# HMS_Olfactometer_v2_1.net
KiCad netlist of a schematic drawn in EAGLE
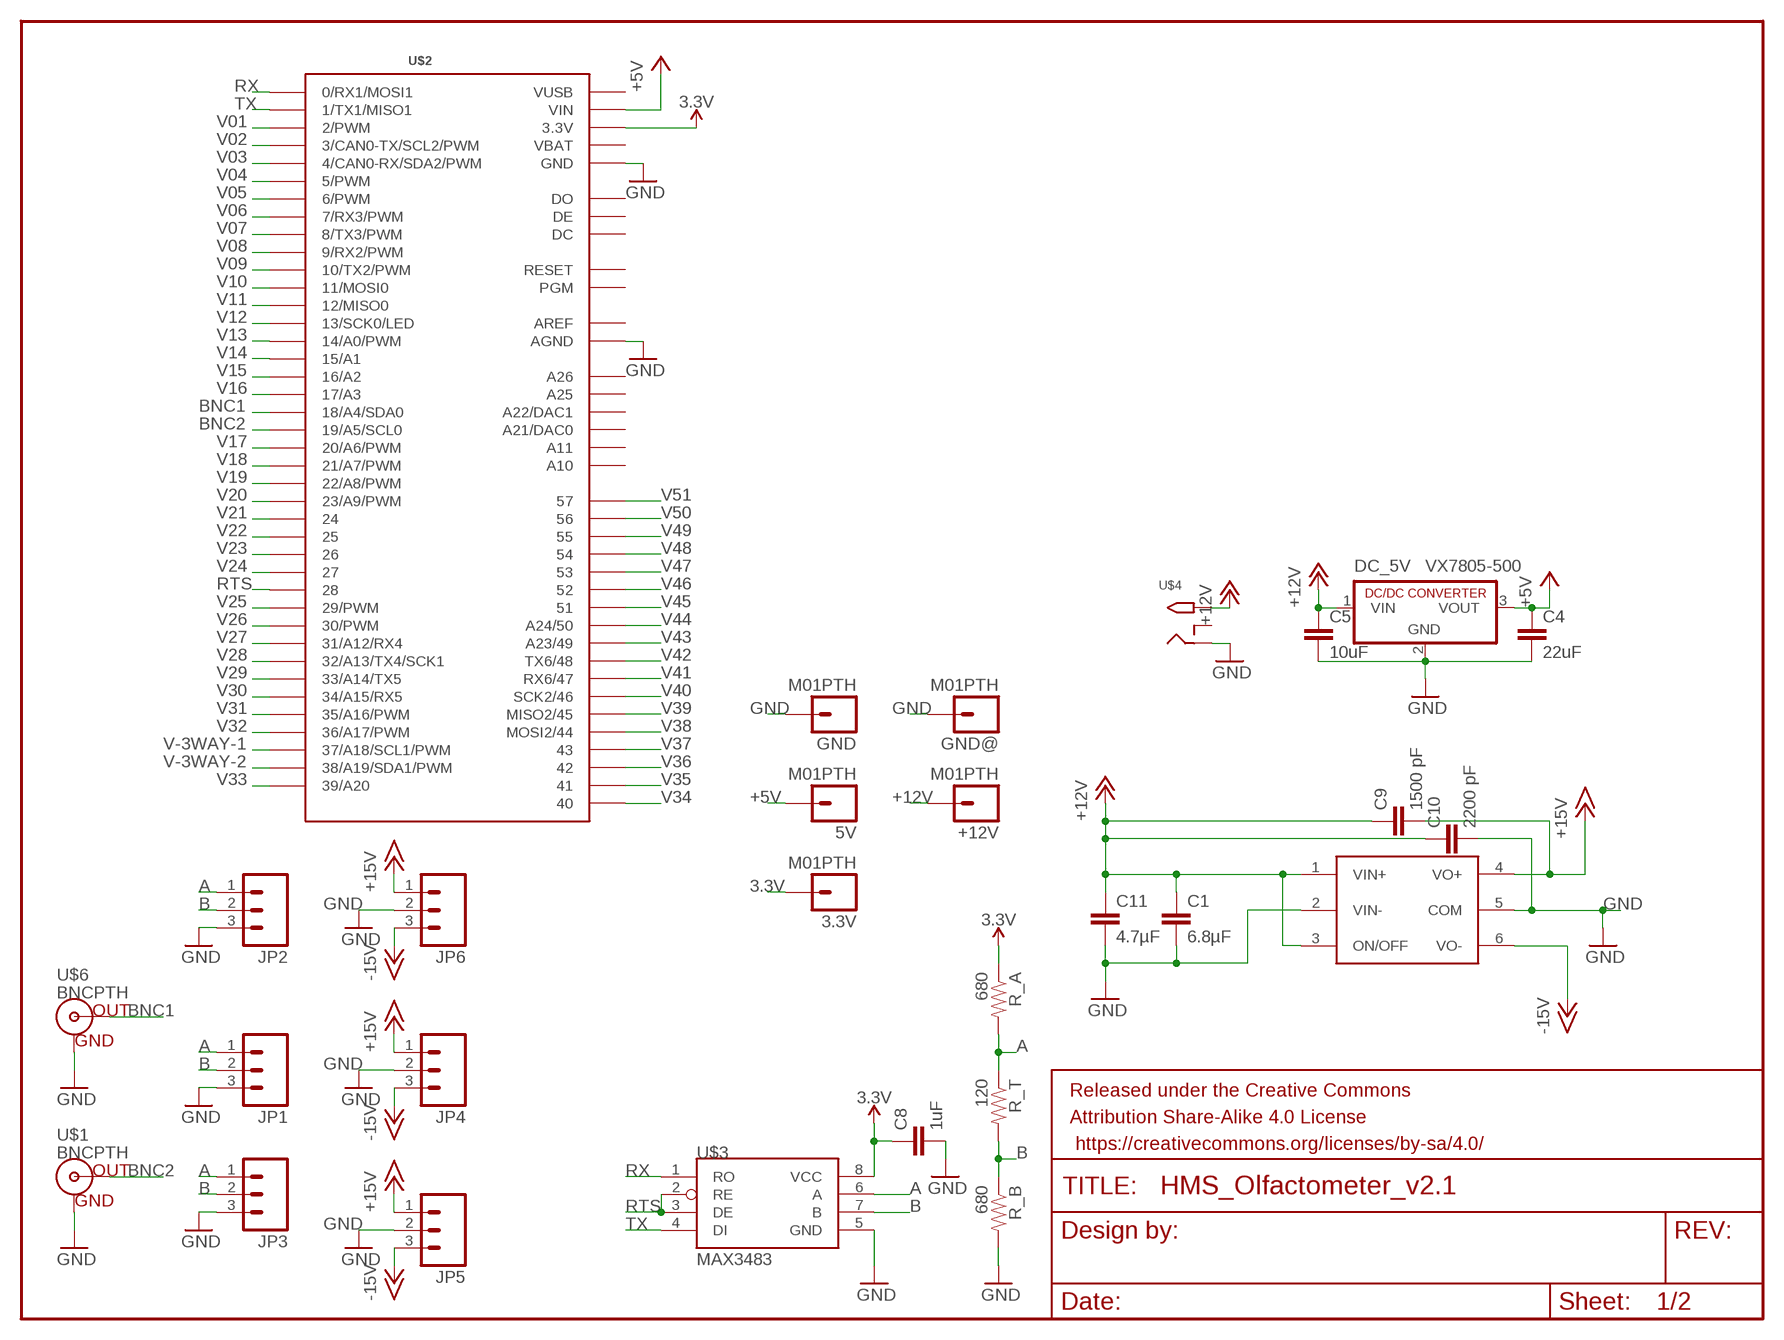
[diagram p0: schematic, sheet 1]
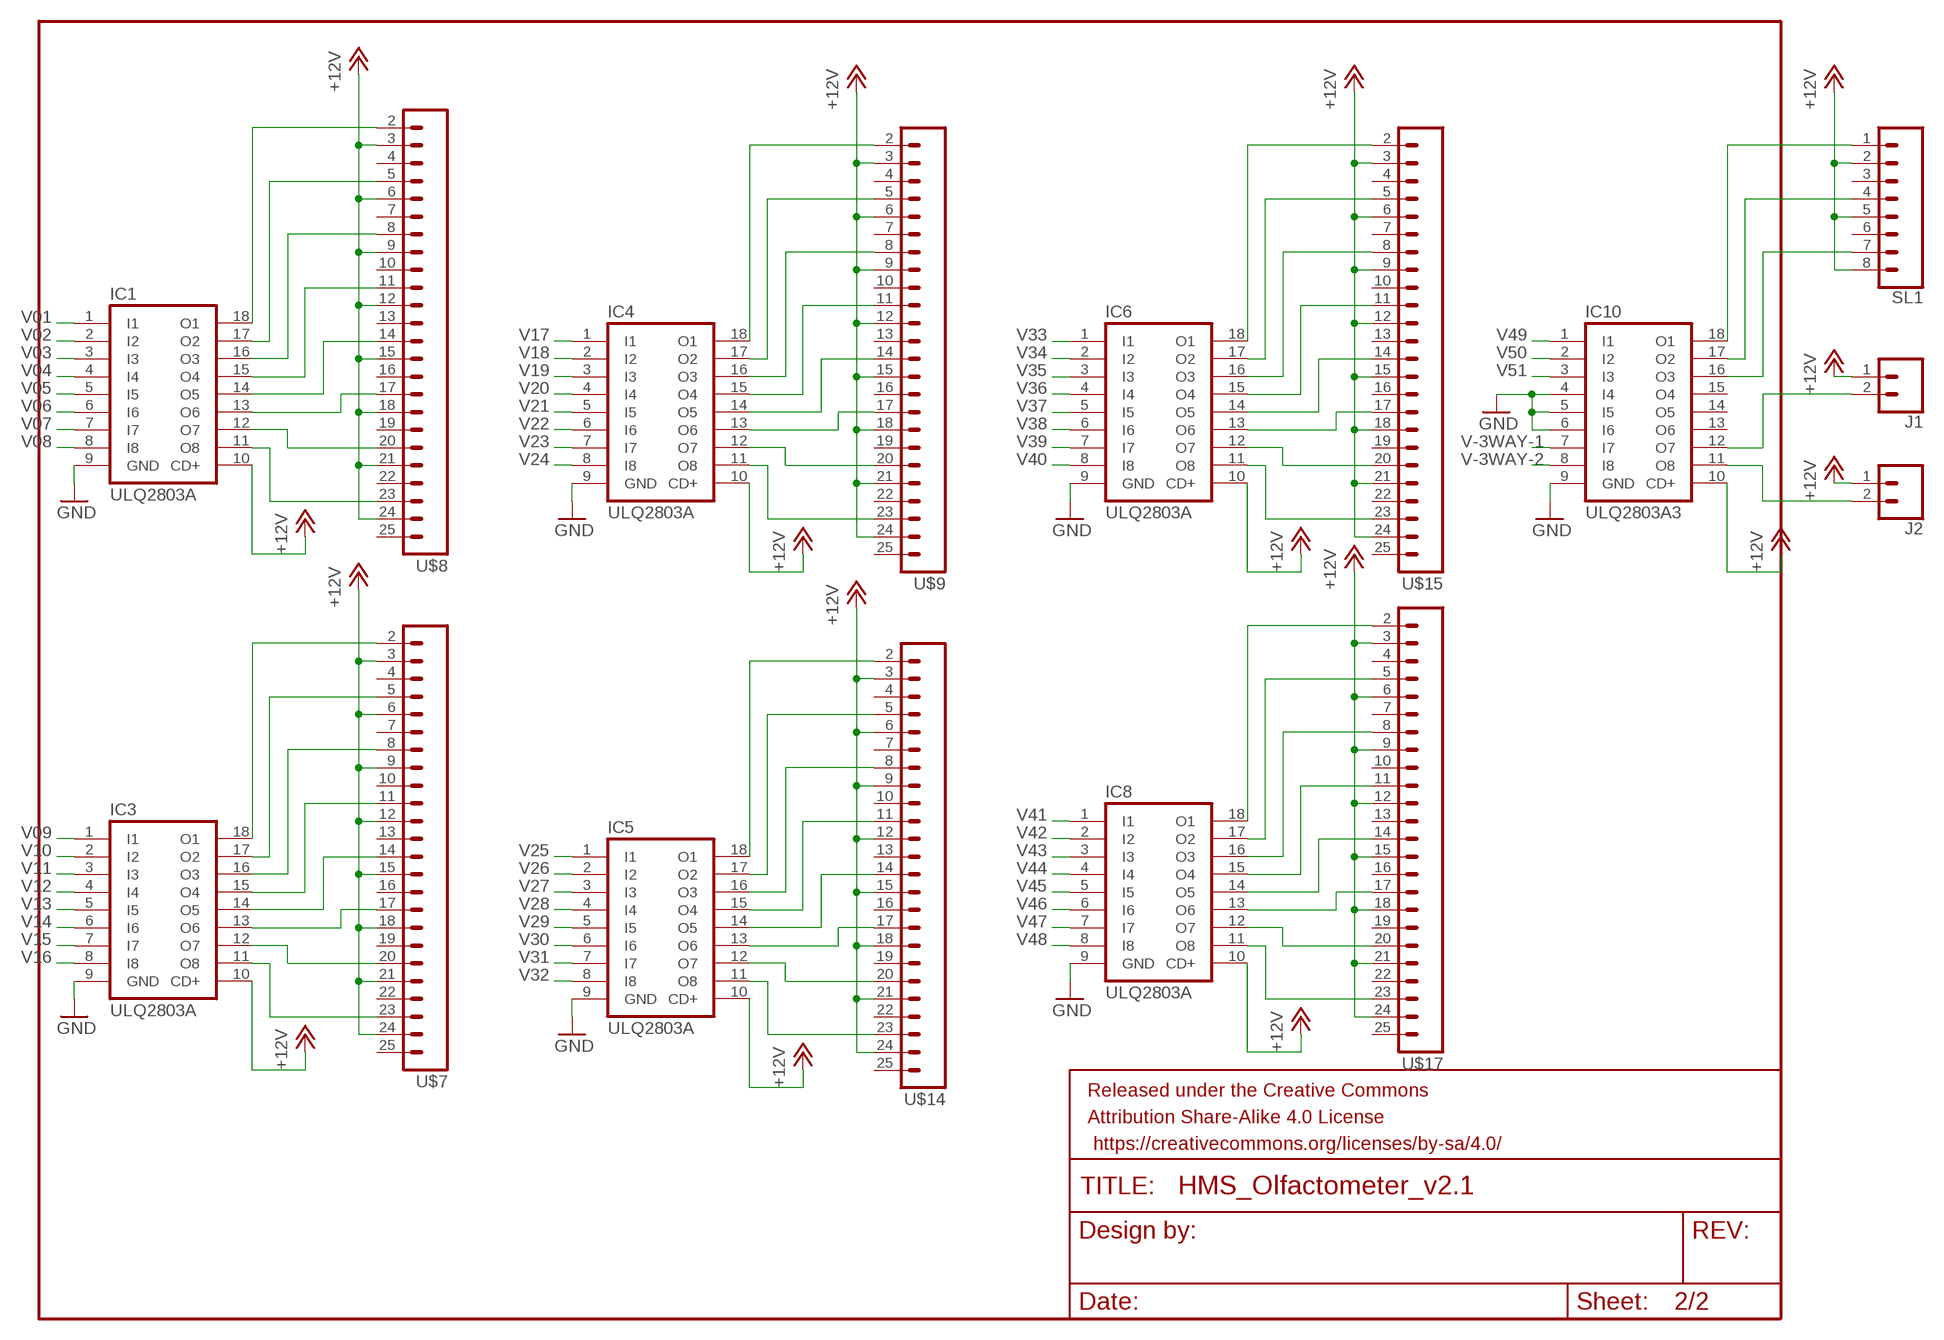
[diagram p1: schematic, sheet 2]

(export (version "E")
  (design (tool "Eeschema 10.0.6"))
  (components
    (comp (ref "FRAME2")
      (value "FRAME-LETTER")
      (footprint "eagle-import:CREATIVE_COMMONS")
      (libsource (lib "eagle-import") (part "FRAME-LETTER"))
    )
    (comp (ref "IC1")
      (value "ULQ2803A")
      (footprint "eagle-import:DIL18")
      (libsource (lib "eagle-import") (part "ULN2803A"))
    )
    (comp (ref "IC3")
      (value "ULQ2803A")
      (footprint "eagle-import:DIL18")
      (libsource (lib "eagle-import") (part "ULN2803A"))
    )
    (comp (ref "IC4")
      (value "ULQ2803A")
      (footprint "eagle-import:DIL18")
      (libsource (lib "eagle-import") (part "ULN2803A"))
    )
    (comp (ref "IC5")
      (value "ULQ2803A")
      (footprint "eagle-import:DIL18")
      (libsource (lib "eagle-import") (part "ULN2803A"))
    )
    (comp (ref "IC6")
      (value "ULQ2803A")
      (footprint "eagle-import:DIL18")
      (libsource (lib "eagle-import") (part "ULN2803A"))
    )
    (comp (ref "IC8")
      (value "ULQ2803A")
      (footprint "eagle-import:DIL18")
      (libsource (lib "eagle-import") (part "ULN2803A"))
    )
    (comp (ref "IC10")
      (value "ULQ2803A3")
      (footprint "eagle-import:DIL18")
      (libsource (lib "eagle-import") (part "ULN2803A"))
    )
    (comp (ref "J1")
      (value "CONN_02")
      (footprint "eagle-import:1X02")
      (libsource (lib "eagle-import") (part "CONN_02"))
    )
    (comp (ref "J2")
      (value "CONN_02")
      (footprint "eagle-import:1X02")
      (libsource (lib "eagle-import") (part "CONN_02"))
    )
    (comp (ref "SL1")
      (value "CONN_08\"")
      (footprint "eagle-import:1X08")
      (libsource (lib "eagle-import") (part "CONN_08{dblquote}"))
    )
    (comp (ref "U$7")
      (value "M24")
      (footprint "eagle-import:1X24")
      (libsource (lib "eagle-import") (part "M24"))
    )
    (comp (ref "U$8")
      (value "M24")
      (footprint "eagle-import:1X24")
      (libsource (lib "eagle-import") (part "M24"))
    )
    (comp (ref "U$9")
      (value "M24")
      (footprint "eagle-import:1X24")
      (libsource (lib "eagle-import") (part "M24"))
    )
    (comp (ref "U$14")
      (value "M24")
      (footprint "eagle-import:1X24")
      (libsource (lib "eagle-import") (part "M24"))
    )
    (comp (ref "U$15")
      (value "M24")
      (footprint "eagle-import:1X24")
      (libsource (lib "eagle-import") (part "M24"))
    )
    (comp (ref "U$17")
      (value "M24")
      (footprint "eagle-import:1X24")
      (libsource (lib "eagle-import") (part "M24"))
    )
    (comp (ref "+12V")
      (value "M01PTH")
      (footprint "eagle-import:1X01")
      (libsource (lib "eagle-import") (part "M01PTH"))
    )
    (comp (ref "3.3V")
      (value "M01PTH")
      (footprint "eagle-import:1X01")
      (libsource (lib "eagle-import") (part "M01PTH"))
    )
    (comp (ref "5V")
      (value "M01PTH")
      (footprint "eagle-import:1X01")
      (libsource (lib "eagle-import") (part "M01PTH"))
    )
    (comp (ref "C1")
      (value "6.8µF")
      (footprint "eagle-import:C1812")
      (libsource (lib "eagle-import") (part "C-EUC1812"))
    )
    (comp (ref "C4")
      (value "22uF")
      (footprint "eagle-import:1206")
      (libsource (lib "eagle-import") (part "10UF-6.3V-20%(1206)"))
    )
    (comp (ref "C5")
      (value "10uF")
      (footprint "eagle-import:1206")
      (libsource (lib "eagle-import") (part "CAP1206"))
    )
    (comp (ref "C8")
      (value "1uF")
      (footprint "eagle-import:1206")
      (libsource (lib "eagle-import") (part "CAP1206"))
    )
    (comp (ref "C9")
      (value "1500 pF")
      (footprint "eagle-import:C1206")
      (libsource (lib "eagle-import") (part "C-EUC1206"))
    )
    (comp (ref "C10")
      (value "2200 pF")
      (footprint "eagle-import:C1206")
      (libsource (lib "eagle-import") (part "C-EUC1206"))
    )
    (comp (ref "C11")
      (value "4.7µF")
      (footprint "eagle-import:C1812")
      (libsource (lib "eagle-import") (part "C-EUC1812"))
    )
    (comp (ref "DC_+/-15V")
      (value "XPPOWER_+/-15V_60W_DC-DC_SUPPLY")
      (footprint "eagle-import:XPPOWER_60W_JTL60_DC_DC_POWER_SUPPLY")
      (libsource (lib "eagle-import") (part "XPPOWER_+/-15V_60W_DC-DC_SUPPLY"))
    )
    (comp (ref "DC_5V")
      (value "VX7805-500")
      (footprint "eagle-import:SIP3")
      (libsource (lib "eagle-import") (part "R-78C-1.012"))
    )
    (comp (ref "FRAME1")
      (value "FRAME-LETTER")
      (footprint "eagle-import:CREATIVE_COMMONS")
      (libsource (lib "eagle-import") (part "FRAME-LETTER"))
    )
    (comp (ref "GND")
      (value "M01PTH")
      (footprint "eagle-import:1X01")
      (libsource (lib "eagle-import") (part "M01PTH"))
    )
    (comp (ref "GND@")
      (value "M01PTH")
      (footprint "eagle-import:1X01")
      (libsource (lib "eagle-import") (part "M01PTH"))
    )
    (comp (ref "JP1")
      (value "M03POLAR")
      (footprint "eagle-import:MOLEX-1X3")
      (libsource (lib "eagle-import") (part "M03POLAR"))
    )
    (comp (ref "JP2")
      (value "M03POLAR")
      (footprint "eagle-import:MOLEX-1X3")
      (libsource (lib "eagle-import") (part "M03POLAR"))
    )
    (comp (ref "JP3")
      (value "M03POLAR")
      (footprint "eagle-import:MOLEX-1X3")
      (libsource (lib "eagle-import") (part "M03POLAR"))
    )
    (comp (ref "JP4")
      (value "M03SCREW")
      (footprint "eagle-import:SCREWTERMINAL-3.5MM-3")
      (libsource (lib "eagle-import") (part "M03SCREW"))
    )
    (comp (ref "JP5")
      (value "M03SCREW")
      (footprint "eagle-import:SCREWTERMINAL-3.5MM-3")
      (libsource (lib "eagle-import") (part "M03SCREW"))
    )
    (comp (ref "JP6")
      (value "M03SCREW")
      (footprint "eagle-import:SCREWTERMINAL-3.5MM-3")
      (libsource (lib "eagle-import") (part "M03SCREW"))
    )
    (comp (ref "R_A")
      (value "680")
      (footprint "eagle-import:AXIAL-0.5")
      (libsource (lib "eagle-import") (part "RESISTORPTH-1/2W"))
    )
    (comp (ref "R_B")
      (value "680")
      (footprint "eagle-import:AXIAL-0.5")
      (libsource (lib "eagle-import") (part "RESISTORPTH-1/2W"))
    )
    (comp (ref "R_T")
      (value "120")
      (footprint "eagle-import:AXIAL-0.5")
      (libsource (lib "eagle-import") (part "RESISTORPTH-1/2W"))
    )
    (comp (ref "U$1")
      (value "BNCPTH")
      (footprint "eagle-import:BNC")
      (libsource (lib "eagle-import") (part "BNCPTH"))
    )
    (comp (ref "U$2")
      (value "TEENSY_3.5_ALL_PINS&PADS")
      (footprint "eagle-import:TEENSY_3.5_ALL_PINS&PADS")
      (libsource (lib "eagle-import") (part "TEENSY_3.5_ALL_PINS&PADS"))
    )
    (comp (ref "U$3")
      (value "MAX3483")
      (footprint "eagle-import:DIL08")
      (fields (field (name "SPICEPREFIX") "X"))
      (libsource (lib "eagle-import") (part "MAX485DIL"))
    )
    (comp (ref "U$4")
      (value "2.1MMJACKTHM")
      (footprint "eagle-import:PJ-102A")
      (libsource (lib "eagle-import") (part "2.1MMJACKTHM"))
    )
    (comp (ref "U$6")
      (value "BNCPTH")
      (footprint "eagle-import:BNC")
      (libsource (lib "eagle-import") (part "BNCPTH"))
    )
  )
  (nets
    (net (code "1") (name "+5V") (class "Default")
      (node (ref "5V") (pin "1") (pinfunction "1_1") (pintype "passive"))
      (node (ref "C4") (pin "1") (pinfunction "1_1") (pintype "passive"))
      (node (ref "DC_5V") (pin "3") (pinfunction "VOUT_3") (pintype "passive"))
      (node (ref "U$2") (pin "VIN") (pinfunction "VIN_VIN") (pintype "power_in"))
    )
    (net (code "2") (name "+12V") (class "Default")
      (node (ref "+12V") (pin "1") (pinfunction "1_1") (pintype "passive"))
      (node (ref "C1") (pin "1") (pinfunction "1_1") (pintype "passive"))
      (node (ref "C10") (pin "1") (pinfunction "1_1") (pintype "passive"))
      (node (ref "C11") (pin "1") (pinfunction "1_1") (pintype "passive"))
      (node (ref "C5") (pin "1") (pinfunction "1_1") (pintype "passive"))
      (node (ref "C9") (pin "1") (pinfunction "1_1") (pintype "passive"))
      (node (ref "DC_+/-15V") (pin "1") (pinfunction "VIN+_1") (pintype "passive"))
      (node (ref "DC_+/-15V") (pin "3") (pinfunction "ON/OFF_3") (pintype "bidirectional"))
      (node (ref "DC_5V") (pin "1") (pinfunction "VIN_1") (pintype "passive"))
      (node (ref "IC1") (pin "10") (pinfunction "CD+_10") (pintype "passive"))
      (node (ref "IC10") (pin "10") (pinfunction "CD+_10") (pintype "passive"))
      (node (ref "IC3") (pin "10") (pinfunction "CD+_10") (pintype "passive"))
      (node (ref "IC4") (pin "10") (pinfunction "CD+_10") (pintype "passive"))
      (node (ref "IC5") (pin "10") (pinfunction "CD+_10") (pintype "passive"))
      (node (ref "IC6") (pin "10") (pinfunction "CD+_10") (pintype "passive"))
      (node (ref "IC8") (pin "10") (pinfunction "CD+_10") (pintype "passive"))
      (node (ref "J1") (pin "1") (pinfunction "1_1") (pintype "passive"))
      (node (ref "J2") (pin "1") (pinfunction "1_1") (pintype "passive"))
      (node (ref "SL1") (pin "2") (pinfunction "2_2") (pintype "passive"))
      (node (ref "SL1") (pin "5") (pinfunction "5_5") (pintype "passive"))
      (node (ref "SL1") (pin "8") (pinfunction "8_8") (pintype "passive"))
      (node (ref "U$14") (pin "12") (pinfunction "12_12") (pintype "passive"))
      (node (ref "U$14") (pin "15") (pinfunction "15_15") (pintype "passive"))
      (node (ref "U$14") (pin "18") (pinfunction "18_18") (pintype "passive"))
      (node (ref "U$14") (pin "21") (pinfunction "21_21") (pintype "passive"))
      (node (ref "U$14") (pin "24") (pinfunction "24_24") (pintype "passive"))
      (node (ref "U$14") (pin "3") (pinfunction "3_3") (pintype "passive"))
      (node (ref "U$14") (pin "6") (pinfunction "6_6") (pintype "passive"))
      (node (ref "U$14") (pin "9") (pinfunction "9_9") (pintype "passive"))
      (node (ref "U$15") (pin "12") (pinfunction "12_12") (pintype "passive"))
      (node (ref "U$15") (pin "15") (pinfunction "15_15") (pintype "passive"))
      (node (ref "U$15") (pin "18") (pinfunction "18_18") (pintype "passive"))
      (node (ref "U$15") (pin "21") (pinfunction "21_21") (pintype "passive"))
      (node (ref "U$15") (pin "24") (pinfunction "24_24") (pintype "passive"))
      (node (ref "U$15") (pin "3") (pinfunction "3_3") (pintype "passive"))
      (node (ref "U$15") (pin "6") (pinfunction "6_6") (pintype "passive"))
      (node (ref "U$15") (pin "9") (pinfunction "9_9") (pintype "passive"))
      (node (ref "U$17") (pin "12") (pinfunction "12_12") (pintype "passive"))
      (node (ref "U$17") (pin "15") (pinfunction "15_15") (pintype "passive"))
      (node (ref "U$17") (pin "18") (pinfunction "18_18") (pintype "passive"))
      (node (ref "U$17") (pin "21") (pinfunction "21_21") (pintype "passive"))
      (node (ref "U$17") (pin "24") (pinfunction "24_24") (pintype "passive"))
      (node (ref "U$17") (pin "3") (pinfunction "3_3") (pintype "passive"))
      (node (ref "U$17") (pin "6") (pinfunction "6_6") (pintype "passive"))
      (node (ref "U$17") (pin "9") (pinfunction "9_9") (pintype "passive"))
      (node (ref "U$4") (pin "TIP") (pinfunction "TIP_TIP") (pintype "bidirectional"))
      (node (ref "U$7") (pin "12") (pinfunction "12_12") (pintype "passive"))
      (node (ref "U$7") (pin "15") (pinfunction "15_15") (pintype "passive"))
      (node (ref "U$7") (pin "18") (pinfunction "18_18") (pintype "passive"))
      (node (ref "U$7") (pin "21") (pinfunction "21_21") (pintype "passive"))
      (node (ref "U$7") (pin "24") (pinfunction "24_24") (pintype "passive"))
      (node (ref "U$7") (pin "3") (pinfunction "3_3") (pintype "passive"))
      (node (ref "U$7") (pin "6") (pinfunction "6_6") (pintype "passive"))
      (node (ref "U$7") (pin "9") (pinfunction "9_9") (pintype "passive"))
      (node (ref "U$8") (pin "12") (pinfunction "12_12") (pintype "passive"))
      (node (ref "U$8") (pin "15") (pinfunction "15_15") (pintype "passive"))
      (node (ref "U$8") (pin "18") (pinfunction "18_18") (pintype "passive"))
      (node (ref "U$8") (pin "21") (pinfunction "21_21") (pintype "passive"))
      (node (ref "U$8") (pin "24") (pinfunction "24_24") (pintype "passive"))
      (node (ref "U$8") (pin "3") (pinfunction "3_3") (pintype "passive"))
      (node (ref "U$8") (pin "6") (pinfunction "6_6") (pintype "passive"))
      (node (ref "U$8") (pin "9") (pinfunction "9_9") (pintype "passive"))
      (node (ref "U$9") (pin "12") (pinfunction "12_12") (pintype "passive"))
      (node (ref "U$9") (pin "15") (pinfunction "15_15") (pintype "passive"))
      (node (ref "U$9") (pin "18") (pinfunction "18_18") (pintype "passive"))
      (node (ref "U$9") (pin "21") (pinfunction "21_21") (pintype "passive"))
      (node (ref "U$9") (pin "24") (pinfunction "24_24") (pintype "passive"))
      (node (ref "U$9") (pin "3") (pinfunction "3_3") (pintype "passive"))
      (node (ref "U$9") (pin "6") (pinfunction "6_6") (pintype "passive"))
      (node (ref "U$9") (pin "9") (pinfunction "9_9") (pintype "passive"))
    )
    (net (code "3") (name "+15V") (class "Default")
      (node (ref "C9") (pin "2") (pinfunction "2_2") (pintype "passive"))
      (node (ref "DC_+/-15V") (pin "4") (pinfunction "VO+_4") (pintype "power_in"))
      (node (ref "JP4") (pin "1") (pinfunction "1_1") (pintype "passive"))
      (node (ref "JP5") (pin "1") (pinfunction "1_1") (pintype "passive"))
      (node (ref "JP6") (pin "1") (pinfunction "1_1") (pintype "passive"))
    )
    (net (code "4") (name "-15V") (class "Default")
      (node (ref "DC_+/-15V") (pin "6") (pinfunction "VO-_6") (pintype "power_in"))
      (node (ref "JP4") (pin "3") (pinfunction "3_3") (pintype "passive"))
      (node (ref "JP5") (pin "3") (pinfunction "3_3") (pintype "passive"))
      (node (ref "JP6") (pin "3") (pinfunction "3_3") (pintype "passive"))
    )
    (net (code "5") (name "3.3V") (class "Default")
      (node (ref "3.3V") (pin "1") (pinfunction "1_1") (pintype "passive"))
      (node (ref "C8") (pin "1") (pinfunction "1_1") (pintype "passive"))
      (node (ref "R_A") (pin "P$1") (pinfunction "1_P$1") (pintype "passive"))
      (node (ref "U$2") (pin "3.3V") (pinfunction "3.3V_3.3V") (pintype "power_in"))
      (node (ref "U$2") (pin "3.3V2") (pinfunction "3.3V_3.3V2") (pintype "power_in"))
      (node (ref "U$2") (pin "3.3V3") (pinfunction "3.3V_3.3V3") (pintype "power_in"))
      (node (ref "U$2") (pin "3.3V4") (pinfunction "3.3V_3.3V4") (pintype "power_in"))
      (node (ref "U$3") (pin "8") (pinfunction "VCC_8") (pintype "bidirectional"))
    )
    (net (code "6") (name "A") (class "Default")
      (node (ref "JP1") (pin "1") (pinfunction "1_1") (pintype "passive"))
      (node (ref "JP2") (pin "1") (pinfunction "1_1") (pintype "passive"))
      (node (ref "JP3") (pin "1") (pinfunction "1_1") (pintype "passive"))
      (node (ref "R_A") (pin "P$2") (pinfunction "2_P$2") (pintype "passive"))
      (node (ref "R_T") (pin "P$1") (pinfunction "1_P$1") (pintype "passive"))
      (node (ref "U$3") (pin "6") (pinfunction "A_6") (pintype "bidirectional"))
    )
    (net (code "7") (name "AREF") (class "Default")
      (node (ref "U$2") (pin "AREF") (pinfunction "AREF_AREF") (pintype "power_in"))
    )
    (net (code "8") (name "B") (class "Default")
      (node (ref "JP1") (pin "2") (pinfunction "2_2") (pintype "passive"))
      (node (ref "JP2") (pin "2") (pinfunction "2_2") (pintype "passive"))
      (node (ref "JP3") (pin "2") (pinfunction "2_2") (pintype "passive"))
      (node (ref "R_B") (pin "P$1") (pinfunction "1_P$1") (pintype "passive"))
      (node (ref "R_T") (pin "P$2") (pinfunction "2_P$2") (pintype "passive"))
      (node (ref "U$3") (pin "7") (pinfunction "B_7") (pintype "bidirectional"))
    )
    (net (code "9") (name "BNC1") (class "Default")
      (node (ref "U$2") (pin "18/A4") (pinfunction "18/A4/SDA0_18/A4") (pintype "bidirectional"))
      (node (ref "U$6") (pin "S") (pinfunction "OUT_S") (pintype "bidirectional"))
    )
    (net (code "10") (name "BNC2") (class "Default")
      (node (ref "U$1") (pin "S") (pinfunction "OUT_S") (pintype "bidirectional"))
      (node (ref "U$2") (pin "19/A5") (pinfunction "19/A5/SCL0_19/A5") (pintype "bidirectional"))
    )
    (net (code "11") (name "GND") (class "Default")
      (node (ref "C1") (pin "2") (pinfunction "2_2") (pintype "passive"))
      (node (ref "C10") (pin "2") (pinfunction "2_2") (pintype "passive"))
      (node (ref "C11") (pin "2") (pinfunction "2_2") (pintype "passive"))
      (node (ref "C4") (pin "2") (pinfunction "2_2") (pintype "passive"))
      (node (ref "C5") (pin "2") (pinfunction "2_2") (pintype "passive"))
      (node (ref "C8") (pin "2") (pinfunction "2_2") (pintype "passive"))
      (node (ref "DC_+/-15V") (pin "2") (pinfunction "VIN-_2") (pintype "power_in"))
      (node (ref "DC_+/-15V") (pin "5") (pinfunction "COM_5") (pintype "power_in"))
      (node (ref "DC_5V") (pin "2") (pinfunction "GND_2") (pintype "passive"))
      (node (ref "GND") (pin "1") (pinfunction "1_1") (pintype "passive"))
      (node (ref "GND@") (pin "1") (pinfunction "1_1") (pintype "passive"))
      (node (ref "IC1") (pin "9") (pinfunction "GND_9") (pintype "power_in"))
      (node (ref "IC10") (pin "4") (pinfunction "I4_4") (pintype "input"))
      (node (ref "IC10") (pin "5") (pinfunction "I5_5") (pintype "input"))
      (node (ref "IC10") (pin "6") (pinfunction "I6_6") (pintype "input"))
      (node (ref "IC10") (pin "9") (pinfunction "GND_9") (pintype "power_in"))
      (node (ref "IC3") (pin "9") (pinfunction "GND_9") (pintype "power_in"))
      (node (ref "IC4") (pin "9") (pinfunction "GND_9") (pintype "power_in"))
      (node (ref "IC5") (pin "9") (pinfunction "GND_9") (pintype "power_in"))
      (node (ref "IC6") (pin "9") (pinfunction "GND_9") (pintype "power_in"))
      (node (ref "IC8") (pin "9") (pinfunction "GND_9") (pintype "power_in"))
      (node (ref "JP1") (pin "3") (pinfunction "3_3") (pintype "passive"))
      (node (ref "JP2") (pin "3") (pinfunction "3_3") (pintype "passive"))
      (node (ref "JP3") (pin "3") (pinfunction "3_3") (pintype "passive"))
      (node (ref "JP4") (pin "2") (pinfunction "2_2") (pintype "passive"))
      (node (ref "JP5") (pin "2") (pinfunction "2_2") (pintype "passive"))
      (node (ref "JP6") (pin "2") (pinfunction "2_2") (pintype "passive"))
      (node (ref "R_B") (pin "P$2") (pinfunction "2_P$2") (pintype "passive"))
      (node (ref "U$1") (pin "GND") (pinfunction "GND_GND") (pintype "bidirectional"))
      (node (ref "U$2") (pin "AGND") (pinfunction "AGND_AGND") (pintype "power_in"))
      (node (ref "U$2") (pin "GND") (pinfunction "GND_GND") (pintype "power_in"))
      (node (ref "U$2") (pin "GND1") (pinfunction "GND_GND1") (pintype "power_in"))
      (node (ref "U$2") (pin "GND2") (pinfunction "GND_GND2") (pintype "power_in"))
      (node (ref "U$2") (pin "GND3") (pinfunction "GND_GND3") (pintype "power_in"))
      (node (ref "U$2") (pin "GND4") (pinfunction "GND_GND4") (pintype "power_in"))
      (node (ref "U$2") (pin "GND5") (pinfunction "GND_GND5") (pintype "power_in"))
      (node (ref "U$2") (pin "GND6") (pinfunction "GND_GND6") (pintype "power_in"))
      (node (ref "U$3") (pin "5") (pinfunction "GND_5") (pintype "bidirectional"))
      (node (ref "U$4") (pin "RING") (pinfunction "RING_RING") (pintype "bidirectional"))
      (node (ref "U$6") (pin "GND") (pinfunction "GND_GND") (pintype "bidirectional"))
    )
    (net (code "12") (name "Net-(IC1-O1)") (class "Default")
      (node (ref "IC1") (pin "18") (pinfunction "O1_18") (pintype "open_collector"))
      (node (ref "U$8") (pin "2") (pinfunction "2_2") (pintype "passive"))
    )
    (net (code "13") (name "Net-(IC1-O2)") (class "Default")
      (node (ref "IC1") (pin "17") (pinfunction "O2_17") (pintype "open_collector"))
      (node (ref "U$8") (pin "5") (pinfunction "5_5") (pintype "passive"))
    )
    (net (code "14") (name "Net-(IC1-O3)") (class "Default")
      (node (ref "IC1") (pin "16") (pinfunction "O3_16") (pintype "open_collector"))
      (node (ref "U$8") (pin "8") (pinfunction "8_8") (pintype "passive"))
    )
    (net (code "15") (name "Net-(IC1-O4)") (class "Default")
      (node (ref "IC1") (pin "15") (pinfunction "O4_15") (pintype "open_collector"))
      (node (ref "U$8") (pin "11") (pinfunction "11_11") (pintype "passive"))
    )
    (net (code "16") (name "Net-(IC1-O5)") (class "Default")
      (node (ref "IC1") (pin "14") (pinfunction "O5_14") (pintype "open_collector"))
      (node (ref "U$8") (pin "14") (pinfunction "14_14") (pintype "passive"))
    )
    (net (code "17") (name "Net-(IC1-O6)") (class "Default")
      (node (ref "IC1") (pin "13") (pinfunction "O6_13") (pintype "open_collector"))
      (node (ref "U$8") (pin "17") (pinfunction "17_17") (pintype "passive"))
    )
    (net (code "18") (name "Net-(IC1-O7)") (class "Default")
      (node (ref "IC1") (pin "12") (pinfunction "O7_12") (pintype "open_collector"))
      (node (ref "U$8") (pin "20") (pinfunction "20_20") (pintype "passive"))
    )
    (net (code "19") (name "Net-(IC1-O8)") (class "Default")
      (node (ref "IC1") (pin "11") (pinfunction "O8_11") (pintype "open_collector"))
      (node (ref "U$8") (pin "23") (pinfunction "23_23") (pintype "passive"))
    )
    (net (code "20") (name "Net-(IC3-O1)") (class "Default")
      (node (ref "IC3") (pin "18") (pinfunction "O1_18") (pintype "open_collector"))
      (node (ref "U$7") (pin "2") (pinfunction "2_2") (pintype "passive"))
    )
    (net (code "21") (name "Net-(IC3-O2)") (class "Default")
      (node (ref "IC3") (pin "17") (pinfunction "O2_17") (pintype "open_collector"))
      (node (ref "U$7") (pin "5") (pinfunction "5_5") (pintype "passive"))
    )
    (net (code "22") (name "Net-(IC3-O3)") (class "Default")
      (node (ref "IC3") (pin "16") (pinfunction "O3_16") (pintype "open_collector"))
      (node (ref "U$7") (pin "8") (pinfunction "8_8") (pintype "passive"))
    )
    (net (code "23") (name "Net-(IC3-O4)") (class "Default")
      (node (ref "IC3") (pin "15") (pinfunction "O4_15") (pintype "open_collector"))
      (node (ref "U$7") (pin "11") (pinfunction "11_11") (pintype "passive"))
    )
    (net (code "24") (name "Net-(IC3-O5)") (class "Default")
      (node (ref "IC3") (pin "14") (pinfunction "O5_14") (pintype "open_collector"))
      (node (ref "U$7") (pin "14") (pinfunction "14_14") (pintype "passive"))
    )
    (net (code "25") (name "Net-(IC3-O6)") (class "Default")
      (node (ref "IC3") (pin "13") (pinfunction "O6_13") (pintype "open_collector"))
      (node (ref "U$7") (pin "17") (pinfunction "17_17") (pintype "passive"))
    )
    (net (code "26") (name "Net-(IC3-O7)") (class "Default")
      (node (ref "IC3") (pin "12") (pinfunction "O7_12") (pintype "open_collector"))
      (node (ref "U$7") (pin "20") (pinfunction "20_20") (pintype "passive"))
    )
    (net (code "27") (name "Net-(IC3-O8)") (class "Default")
      (node (ref "IC3") (pin "11") (pinfunction "O8_11") (pintype "open_collector"))
      (node (ref "U$7") (pin "23") (pinfunction "23_23") (pintype "passive"))
    )
    (net (code "28") (name "Net-(IC4-O1)") (class "Default")
      (node (ref "IC4") (pin "18") (pinfunction "O1_18") (pintype "open_collector"))
      (node (ref "U$9") (pin "2") (pinfunction "2_2") (pintype "passive"))
    )
    (net (code "29") (name "Net-(IC4-O2)") (class "Default")
      (node (ref "IC4") (pin "17") (pinfunction "O2_17") (pintype "open_collector"))
      (node (ref "U$9") (pin "5") (pinfunction "5_5") (pintype "passive"))
    )
    (net (code "30") (name "Net-(IC4-O3)") (class "Default")
      (node (ref "IC4") (pin "16") (pinfunction "O3_16") (pintype "open_collector"))
      (node (ref "U$9") (pin "8") (pinfunction "8_8") (pintype "passive"))
    )
    (net (code "31") (name "Net-(IC4-O4)") (class "Default")
      (node (ref "IC4") (pin "15") (pinfunction "O4_15") (pintype "open_collector"))
      (node (ref "U$9") (pin "11") (pinfunction "11_11") (pintype "passive"))
    )
    (net (code "32") (name "Net-(IC4-O5)") (class "Default")
      (node (ref "IC4") (pin "14") (pinfunction "O5_14") (pintype "open_collector"))
      (node (ref "U$9") (pin "14") (pinfunction "14_14") (pintype "passive"))
    )
    (net (code "33") (name "Net-(IC4-O6)") (class "Default")
      (node (ref "IC4") (pin "13") (pinfunction "O6_13") (pintype "open_collector"))
      (node (ref "U$9") (pin "17") (pinfunction "17_17") (pintype "passive"))
    )
    (net (code "34") (name "Net-(IC4-O7)") (class "Default")
      (node (ref "IC4") (pin "12") (pinfunction "O7_12") (pintype "open_collector"))
      (node (ref "U$9") (pin "20") (pinfunction "20_20") (pintype "passive"))
    )
    (net (code "35") (name "Net-(IC4-O8)") (class "Default")
      (node (ref "IC4") (pin "11") (pinfunction "O8_11") (pintype "open_collector"))
      (node (ref "U$9") (pin "23") (pinfunction "23_23") (pintype "passive"))
    )
    (net (code "36") (name "Net-(IC5-O1)") (class "Default")
      (node (ref "IC5") (pin "18") (pinfunction "O1_18") (pintype "open_collector"))
      (node (ref "U$14") (pin "2") (pinfunction "2_2") (pintype "passive"))
    )
    (net (code "37") (name "Net-(IC5-O2)") (class "Default")
      (node (ref "IC5") (pin "17") (pinfunction "O2_17") (pintype "open_collector"))
      (node (ref "U$14") (pin "5") (pinfunction "5_5") (pintype "passive"))
    )
    (net (code "38") (name "Net-(IC5-O3)") (class "Default")
      (node (ref "IC5") (pin "16") (pinfunction "O3_16") (pintype "open_collector"))
      (node (ref "U$14") (pin "8") (pinfunction "8_8") (pintype "passive"))
    )
    (net (code "39") (name "Net-(IC5-O4)") (class "Default")
      (node (ref "IC5") (pin "15") (pinfunction "O4_15") (pintype "open_collector"))
      (node (ref "U$14") (pin "11") (pinfunction "11_11") (pintype "passive"))
    )
    (net (code "40") (name "Net-(IC5-O5)") (class "Default")
      (node (ref "IC5") (pin "14") (pinfunction "O5_14") (pintype "open_collector"))
      (node (ref "U$14") (pin "14") (pinfunction "14_14") (pintype "passive"))
    )
    (net (code "41") (name "Net-(IC5-O6)") (class "Default")
      (node (ref "IC5") (pin "13") (pinfunction "O6_13") (pintype "open_collector"))
      (node (ref "U$14") (pin "17") (pinfunction "17_17") (pintype "passive"))
    )
    (net (code "42") (name "Net-(IC5-O7)") (class "Default")
      (node (ref "IC5") (pin "12") (pinfunction "O7_12") (pintype "open_collector"))
      (node (ref "U$14") (pin "20") (pinfunction "20_20") (pintype "passive"))
    )
    (net (code "43") (name "Net-(IC5-O8)") (class "Default")
      (node (ref "IC5") (pin "11") (pinfunction "O8_11") (pintype "open_collector"))
      (node (ref "U$14") (pin "23") (pinfunction "23_23") (pintype "passive"))
    )
    (net (code "44") (name "Net-(IC6-O1)") (class "Default")
      (node (ref "IC6") (pin "18") (pinfunction "O1_18") (pintype "open_collector"))
      (node (ref "U$15") (pin "2") (pinfunction "2_2") (pintype "passive"))
    )
    (net (code "45") (name "Net-(IC6-O2)") (class "Default")
      (node (ref "IC6") (pin "17") (pinfunction "O2_17") (pintype "open_collector"))
      (node (ref "U$15") (pin "5") (pinfunction "5_5") (pintype "passive"))
    )
    (net (code "46") (name "Net-(IC6-O3)") (class "Default")
      (node (ref "IC6") (pin "16") (pinfunction "O3_16") (pintype "open_collector"))
      (node (ref "U$15") (pin "8") (pinfunction "8_8") (pintype "passive"))
    )
    (net (code "47") (name "Net-(IC6-O4)") (class "Default")
      (node (ref "IC6") (pin "15") (pinfunction "O4_15") (pintype "open_collector"))
      (node (ref "U$15") (pin "11") (pinfunction "11_11") (pintype "passive"))
    )
    (net (code "48") (name "Net-(IC6-O5)") (class "Default")
      (node (ref "IC6") (pin "14") (pinfunction "O5_14") (pintype "open_collector"))
      (node (ref "U$15") (pin "14") (pinfunction "14_14") (pintype "passive"))
    )
    (net (code "49") (name "Net-(IC6-O6)") (class "Default")
      (node (ref "IC6") (pin "13") (pinfunction "O6_13") (pintype "open_collector"))
      (node (ref "U$15") (pin "17") (pinfunction "17_17") (pintype "passive"))
    )
    (net (code "50") (name "Net-(IC6-O7)") (class "Default")
      (node (ref "IC6") (pin "12") (pinfunction "O7_12") (pintype "open_collector"))
      (node (ref "U$15") (pin "20") (pinfunction "20_20") (pintype "passive"))
    )
    (net (code "51") (name "Net-(IC6-O8)") (class "Default")
      (node (ref "IC6") (pin "11") (pinfunction "O8_11") (pintype "open_collector"))
      (node (ref "U$15") (pin "23") (pinfunction "23_23") (pintype "passive"))
    )
    (net (code "52") (name "Net-(IC8-O1)") (class "Default")
      (node (ref "IC8") (pin "18") (pinfunction "O1_18") (pintype "open_collector"))
      (node (ref "U$17") (pin "2") (pinfunction "2_2") (pintype "passive"))
    )
    (net (code "53") (name "Net-(IC8-O2)") (class "Default")
      (node (ref "IC8") (pin "17") (pinfunction "O2_17") (pintype "open_collector"))
      (node (ref "U$17") (pin "5") (pinfunction "5_5") (pintype "passive"))
    )
    (net (code "54") (name "Net-(IC8-O3)") (class "Default")
      (node (ref "IC8") (pin "16") (pinfunction "O3_16") (pintype "open_collector"))
      (node (ref "U$17") (pin "8") (pinfunction "8_8") (pintype "passive"))
    )
    (net (code "55") (name "Net-(IC8-O4)") (class "Default")
      (node (ref "IC8") (pin "15") (pinfunction "O4_15") (pintype "open_collector"))
      (node (ref "U$17") (pin "11") (pinfunction "11_11") (pintype "passive"))
    )
    (net (code "56") (name "Net-(IC8-O5)") (class "Default")
      (node (ref "IC8") (pin "14") (pinfunction "O5_14") (pintype "open_collector"))
      (node (ref "U$17") (pin "14") (pinfunction "14_14") (pintype "passive"))
    )
    (net (code "57") (name "Net-(IC8-O6)") (class "Default")
      (node (ref "IC8") (pin "13") (pinfunction "O6_13") (pintype "open_collector"))
      (node (ref "U$17") (pin "17") (pinfunction "17_17") (pintype "passive"))
    )
    (net (code "58") (name "Net-(IC8-O7)") (class "Default")
      (node (ref "IC8") (pin "12") (pinfunction "O7_12") (pintype "open_collector"))
      (node (ref "U$17") (pin "20") (pinfunction "20_20") (pintype "passive"))
    )
    (net (code "59") (name "Net-(IC8-O8)") (class "Default")
      (node (ref "IC8") (pin "11") (pinfunction "O8_11") (pintype "open_collector"))
      (node (ref "U$17") (pin "23") (pinfunction "23_23") (pintype "passive"))
    )
    (net (code "60") (name "Net-(IC10-O1)") (class "Default")
      (node (ref "IC10") (pin "18") (pinfunction "O1_18") (pintype "open_collector"))
      (node (ref "SL1") (pin "1") (pinfunction "1_1") (pintype "passive"))
    )
    (net (code "61") (name "Net-(IC10-O2)") (class "Default")
      (node (ref "IC10") (pin "17") (pinfunction "O2_17") (pintype "open_collector"))
      (node (ref "SL1") (pin "4") (pinfunction "4_4") (pintype "passive"))
    )
    (net (code "62") (name "Net-(IC10-O3)") (class "Default")
      (node (ref "IC10") (pin "16") (pinfunction "O3_16") (pintype "open_collector"))
      (node (ref "SL1") (pin "7") (pinfunction "7_7") (pintype "passive"))
    )
    (net (code "63") (name "Net-(IC10-O7)") (class "Default")
      (node (ref "IC10") (pin "12") (pinfunction "O7_12") (pintype "open_collector"))
      (node (ref "J1") (pin "2") (pinfunction "2_2") (pintype "passive"))
    )
    (net (code "64") (name "Net-(IC10-O8)") (class "Default")
      (node (ref "IC10") (pin "11") (pinfunction "O8_11") (pintype "open_collector"))
      (node (ref "J2") (pin "2") (pinfunction "2_2") (pintype "passive"))
    )
    (net (code "65") (name "RTS") (class "Default")
      (node (ref "U$2") (pin "28") (pinfunction "28_28") (pintype "bidirectional"))
      (node (ref "U$3") (pin "2") (pinfunction "RE_2") (pintype "bidirectional"))
      (node (ref "U$3") (pin "3") (pinfunction "DE_3") (pintype "bidirectional"))
    )
    (net (code "66") (name "RX") (class "Default")
      (node (ref "U$2") (pin "0") (pinfunction "0/RX1/MOSI1_0") (pintype "bidirectional"))
      (node (ref "U$3") (pin "1") (pinfunction "RO_1") (pintype "bidirectional"))
    )
    (net (code "67") (name "TX") (class "Default")
      (node (ref "U$2") (pin "1") (pinfunction "1/TX1/MISO1_1") (pintype "bidirectional"))
      (node (ref "U$3") (pin "4") (pinfunction "DI_4") (pintype "bidirectional"))
    )
    (net (code "68") (name "V-3WAY-1") (class "Default")
      (node (ref "IC10") (pin "7") (pinfunction "I7_7") (pintype "input"))
      (node (ref "U$2") (pin "37/A18") (pinfunction "37/A18/SCL1/PWM_37/A18") (pintype "bidirectional"))
    )
    (net (code "69") (name "V-3WAY-2") (class "Default")
      (node (ref "IC10") (pin "8") (pinfunction "I8_8") (pintype "input"))
      (node (ref "U$2") (pin "38/A19") (pinfunction "38/A19/SDA1/PWM_38/A19") (pintype "bidirectional"))
    )
    (net (code "70") (name "V01") (class "Default")
      (node (ref "IC1") (pin "1") (pinfunction "I1_1") (pintype "input"))
      (node (ref "U$2") (pin "2") (pinfunction "2/PWM_2") (pintype "bidirectional"))
    )
    (net (code "71") (name "V02") (class "Default")
      (node (ref "IC1") (pin "2") (pinfunction "I2_2") (pintype "input"))
      (node (ref "U$2") (pin "3") (pinfunction "3/CAN0-TX/SCL2/PWM_3") (pintype "bidirectional"))
    )
    (net (code "72") (name "V03") (class "Default")
      (node (ref "IC1") (pin "3") (pinfunction "I3_3") (pintype "input"))
      (node (ref "U$2") (pin "4") (pinfunction "4/CAN0-RX/SDA2/PWM_4") (pintype "bidirectional"))
    )
    (net (code "73") (name "V04") (class "Default")
      (node (ref "IC1") (pin "4") (pinfunction "I4_4") (pintype "input"))
      (node (ref "U$2") (pin "5") (pinfunction "5/PWM_5") (pintype "bidirectional"))
    )
    (net (code "74") (name "V05") (class "Default")
      (node (ref "IC1") (pin "5") (pinfunction "I5_5") (pintype "input"))
      (node (ref "U$2") (pin "6") (pinfunction "6/PWM_6") (pintype "bidirectional"))
    )
    (net (code "75") (name "V06") (class "Default")
      (node (ref "IC1") (pin "6") (pinfunction "I6_6") (pintype "input"))
      (node (ref "U$2") (pin "7") (pinfunction "7/RX3/PWM_7") (pintype "bidirectional"))
    )
    (net (code "76") (name "V07") (class "Default")
      (node (ref "IC1") (pin "7") (pinfunction "I7_7") (pintype "input"))
      (node (ref "U$2") (pin "8") (pinfunction "8/TX3/PWM_8") (pintype "bidirectional"))
    )
    (net (code "77") (name "V08") (class "Default")
      (node (ref "IC1") (pin "8") (pinfunction "I8_8") (pintype "input"))
      (node (ref "U$2") (pin "9") (pinfunction "9/RX2/PWM_9") (pintype "bidirectional"))
    )
    (net (code "78") (name "V09") (class "Default")
      (node (ref "IC3") (pin "1") (pinfunction "I1_1") (pintype "input"))
      (node (ref "U$2") (pin "10") (pinfunction "10/TX2/PWM_10") (pintype "bidirectional"))
    )
    (net (code "79") (name "V10") (class "Default")
      (node (ref "IC3") (pin "2") (pinfunction "I2_2") (pintype "input"))
      (node (ref "U$2") (pin "11") (pinfunction "11/MOSI0_11") (pintype "bidirectional"))
    )
    (net (code "80") (name "V11") (class "Default")
      (node (ref "IC3") (pin "3") (pinfunction "I3_3") (pintype "input"))
      (node (ref "U$2") (pin "12") (pinfunction "12/MISO0_12") (pintype "bidirectional"))
    )
    (net (code "81") (name "V12") (class "Default")
      (node (ref "IC3") (pin "4") (pinfunction "I4_4") (pintype "input"))
      (node (ref "U$2") (pin "13") (pinfunction "13/SCK0/LED_13") (pintype "bidirectional"))
    )
    (net (code "82") (name "V13") (class "Default")
      (node (ref "IC3") (pin "5") (pinfunction "I5_5") (pintype "input"))
      (node (ref "U$2") (pin "14/A0") (pinfunction "14/A0/PWM_14/A0") (pintype "bidirectional"))
    )
    (net (code "83") (name "V14") (class "Default")
      (node (ref "IC3") (pin "6") (pinfunction "I6_6") (pintype "input"))
      (node (ref "U$2") (pin "15/A1") (pinfunction "15/A1_15/A1") (pintype "bidirectional"))
    )
    (net (code "84") (name "V15") (class "Default")
      (node (ref "IC3") (pin "7") (pinfunction "I7_7") (pintype "input"))
      (node (ref "U$2") (pin "16/A2") (pinfunction "16/A2_16/A2") (pintype "bidirectional"))
    )
    (net (code "85") (name "V16") (class "Default")
      (node (ref "IC3") (pin "8") (pinfunction "I8_8") (pintype "input"))
      (node (ref "U$2") (pin "17/A3") (pinfunction "17/A3_17/A3") (pintype "bidirectional"))
    )
    (net (code "86") (name "V17") (class "Default")
      (node (ref "IC4") (pin "1") (pinfunction "I1_1") (pintype "input"))
      (node (ref "U$2") (pin "20/A6") (pinfunction "20/A6/PWM_20/A6") (pintype "bidirectional"))
    )
    (net (code "87") (name "V18") (class "Default")
      (node (ref "IC4") (pin "2") (pinfunction "I2_2") (pintype "input"))
      (node (ref "U$2") (pin "21/A7") (pinfunction "21/A7/PWM_21/A7") (pintype "bidirectional"))
    )
    (net (code "88") (name "V19") (class "Default")
      (node (ref "IC4") (pin "3") (pinfunction "I3_3") (pintype "input"))
      (node (ref "U$2") (pin "22/A8") (pinfunction "22/A8/PWM_22/A8") (pintype "bidirectional"))
    )
    (net (code "89") (name "V20") (class "Default")
      (node (ref "IC4") (pin "4") (pinfunction "I4_4") (pintype "input"))
      (node (ref "U$2") (pin "23/A9") (pinfunction "23/A9/PWM_23/A9") (pintype "bidirectional"))
    )
    (net (code "90") (name "V21") (class "Default")
      (node (ref "IC4") (pin "5") (pinfunction "I5_5") (pintype "input"))
      (node (ref "U$2") (pin "24") (pinfunction "24_24") (pintype "bidirectional"))
    )
    (net (code "91") (name "V22") (class "Default")
      (node (ref "IC4") (pin "6") (pinfunction "I6_6") (pintype "input"))
      (node (ref "U$2") (pin "25") (pinfunction "25_25") (pintype "bidirectional"))
    )
    (net (code "92") (name "V23") (class "Default")
      (node (ref "IC4") (pin "7") (pinfunction "I7_7") (pintype "input"))
      (node (ref "U$2") (pin "26") (pinfunction "26_26") (pintype "bidirectional"))
    )
    (net (code "93") (name "V24") (class "Default")
      (node (ref "IC4") (pin "8") (pinfunction "I8_8") (pintype "input"))
      (node (ref "U$2") (pin "27") (pinfunction "27_27") (pintype "bidirectional"))
    )
    (net (code "94") (name "V25") (class "Default")
      (node (ref "IC5") (pin "1") (pinfunction "I1_1") (pintype "input"))
      (node (ref "U$2") (pin "29") (pinfunction "29/PWM_29") (pintype "bidirectional"))
    )
    (net (code "95") (name "V26") (class "Default")
      (node (ref "IC5") (pin "2") (pinfunction "I2_2") (pintype "input"))
      (node (ref "U$2") (pin "30") (pinfunction "30/PWM_30") (pintype "bidirectional"))
    )
    (net (code "96") (name "V27") (class "Default")
      (node (ref "IC5") (pin "3") (pinfunction "I3_3") (pintype "input"))
      (node (ref "U$2") (pin "31/A12") (pinfunction "31/A12/RX4_31/A12") (pintype "bidirectional"))
    )
    (net (code "97") (name "V28") (class "Default")
      (node (ref "IC5") (pin "4") (pinfunction "I4_4") (pintype "input"))
      (node (ref "U$2") (pin "32/A13") (pinfunction "32/A13/TX4/SCK1_32/A13") (pintype "bidirectional"))
    )
    (net (code "98") (name "V29") (class "Default")
      (node (ref "IC5") (pin "5") (pinfunction "I5_5") (pintype "input"))
      (node (ref "U$2") (pin "33/A14") (pinfunction "33/A14/TX5_33/A14") (pintype "bidirectional"))
    )
    (net (code "99") (name "V30") (class "Default")
      (node (ref "IC5") (pin "6") (pinfunction "I6_6") (pintype "input"))
      (node (ref "U$2") (pin "34/A15") (pinfunction "34/A15/RX5_34/A15") (pintype "bidirectional"))
    )
    (net (code "100") (name "V31") (class "Default")
      (node (ref "IC5") (pin "7") (pinfunction "I7_7") (pintype "input"))
      (node (ref "U$2") (pin "35/A16") (pinfunction "35/A16/PWM_35/A16") (pintype "bidirectional"))
    )
    (net (code "101") (name "V32") (class "Default")
      (node (ref "IC5") (pin "8") (pinfunction "I8_8") (pintype "input"))
      (node (ref "U$2") (pin "36/A17") (pinfunction "36/A17/PWM_36/A17") (pintype "bidirectional"))
    )
    (net (code "102") (name "V33") (class "Default")
      (node (ref "IC6") (pin "1") (pinfunction "I1_1") (pintype "input"))
      (node (ref "U$2") (pin "39/A20") (pinfunction "39/A20_39/A20") (pintype "bidirectional"))
    )
    (net (code "103") (name "V34") (class "Default")
      (node (ref "IC6") (pin "2") (pinfunction "I2_2") (pintype "input"))
      (node (ref "U$2") (pin "40") (pinfunction "40_40") (pintype "bidirectional"))
    )
    (net (code "104") (name "V35") (class "Default")
      (node (ref "IC6") (pin "3") (pinfunction "I3_3") (pintype "input"))
      (node (ref "U$2") (pin "41") (pinfunction "41_41") (pintype "bidirectional"))
    )
    (net (code "105") (name "V36") (class "Default")
      (node (ref "IC6") (pin "4") (pinfunction "I4_4") (pintype "input"))
      (node (ref "U$2") (pin "42") (pinfunction "42_42") (pintype "bidirectional"))
    )
    (net (code "106") (name "V37") (class "Default")
      (node (ref "IC6") (pin "5") (pinfunction "I5_5") (pintype "input"))
      (node (ref "U$2") (pin "43") (pinfunction "43_43") (pintype "bidirectional"))
    )
    (net (code "107") (name "V38") (class "Default")
      (node (ref "IC6") (pin "6") (pinfunction "I6_6") (pintype "input"))
      (node (ref "U$2") (pin "44") (pinfunction "MOSI2/44_44") (pintype "bidirectional"))
    )
    (net (code "108") (name "V39") (class "Default")
      (node (ref "IC6") (pin "7") (pinfunction "I7_7") (pintype "input"))
      (node (ref "U$2") (pin "45") (pinfunction "MISO2/45_45") (pintype "bidirectional"))
    )
    (net (code "109") (name "V40") (class "Default")
      (node (ref "IC6") (pin "8") (pinfunction "I8_8") (pintype "input"))
      (node (ref "U$2") (pin "46") (pinfunction "SCK2/46_46") (pintype "bidirectional"))
    )
    (net (code "110") (name "V41") (class "Default")
      (node (ref "IC8") (pin "1") (pinfunction "I1_1") (pintype "input"))
      (node (ref "U$2") (pin "47") (pinfunction "RX6/47_47") (pintype "bidirectional"))
    )
    (net (code "111") (name "V42") (class "Default")
      (node (ref "IC8") (pin "2") (pinfunction "I2_2") (pintype "input"))
      (node (ref "U$2") (pin "48") (pinfunction "TX6/48_48") (pintype "bidirectional"))
    )
    (net (code "112") (name "V43") (class "Default")
      (node (ref "IC8") (pin "3") (pinfunction "I3_3") (pintype "input"))
      (node (ref "U$2") (pin "49") (pinfunction "A23/49_49") (pintype "bidirectional"))
    )
    (net (code "113") (name "V44") (class "Default")
      (node (ref "IC8") (pin "4") (pinfunction "I4_4") (pintype "input"))
      (node (ref "U$2") (pin "50") (pinfunction "A24/50_50") (pintype "bidirectional"))
    )
    (net (code "114") (name "V45") (class "Default")
      (node (ref "IC8") (pin "5") (pinfunction "I5_5") (pintype "input"))
      (node (ref "U$2") (pin "51") (pinfunction "51_51") (pintype "bidirectional"))
    )
    (net (code "115") (name "V46") (class "Default")
      (node (ref "IC8") (pin "6") (pinfunction "I6_6") (pintype "input"))
      (node (ref "U$2") (pin "52") (pinfunction "52_52") (pintype "bidirectional"))
    )
    (net (code "116") (name "V47") (class "Default")
      (node (ref "IC8") (pin "7") (pinfunction "I7_7") (pintype "input"))
      (node (ref "U$2") (pin "53") (pinfunction "53_53") (pintype "bidirectional"))
    )
    (net (code "117") (name "V48") (class "Default")
      (node (ref "IC8") (pin "8") (pinfunction "I8_8") (pintype "input"))
      (node (ref "U$2") (pin "54") (pinfunction "54_54") (pintype "bidirectional"))
    )
    (net (code "118") (name "V49") (class "Default")
      (node (ref "IC10") (pin "1") (pinfunction "I1_1") (pintype "input"))
      (node (ref "U$2") (pin "55") (pinfunction "55_55") (pintype "bidirectional"))
    )
    (net (code "119") (name "V50") (class "Default")
      (node (ref "IC10") (pin "2") (pinfunction "I2_2") (pintype "input"))
      (node (ref "U$2") (pin "56") (pinfunction "56_56") (pintype "bidirectional"))
    )
    (net (code "120") (name "V51") (class "Default")
      (node (ref "IC10") (pin "3") (pinfunction "I3_3") (pintype "input"))
      (node (ref "U$2") (pin "57") (pinfunction "57_57") (pintype "bidirectional"))
    )
    (net (code "121") (name "VBAT") (class "Default")
      (node (ref "U$2") (pin "VBAT") (pinfunction "VBAT_VBAT") (pintype "power_in"))
    )
    (net (code "122") (name "VUSB") (class "Default")
      (node (ref "U$2") (pin "VUSB") (pinfunction "VUSB_VUSB") (pintype "power_in"))
    )
    (net (code "123") (name "unconnected-(IC10-O4-Pad15)") (class "Default")
      (node (ref "IC10") (pin "15") (pinfunction "O4_15") (pintype "open_collector"))
    )
    (net (code "124") (name "unconnected-(IC10-O5-Pad14)") (class "Default")
      (node (ref "IC10") (pin "14") (pinfunction "O5_14") (pintype "open_collector"))
    )
    (net (code "125") (name "unconnected-(IC10-O6-Pad13)") (class "Default")
      (node (ref "IC10") (pin "13") (pinfunction "O6_13") (pintype "open_collector"))
    )
    (net (code "126") (name "unconnected-(SL1-Pad3)") (class "Default")
      (node (ref "SL1") (pin "3") (pinfunction "3_3") (pintype "passive"))
    )
    (net (code "127") (name "unconnected-(SL1-Pad6)") (class "Default")
      (node (ref "SL1") (pin "6") (pinfunction "6_6") (pintype "passive"))
    )
    (net (code "128") (name "unconnected-(U$2-A21{slash}DAC0-PadA21)") (class "Default")
      (node (ref "U$2") (pin "A21") (pinfunction "A21/DAC0_A21") (pintype "bidirectional"))
    )
    (net (code "129") (name "unconnected-(U$2-A22{slash}DAC1-PadA22)") (class "Default")
      (node (ref "U$2") (pin "A22") (pinfunction "A22/DAC1_A22") (pintype "bidirectional"))
    )
    (net (code "130") (name "unconnected-(U$2-PadA10)") (class "Default")
      (node (ref "U$2") (pin "A10") (pinfunction "A10_A10") (pintype "bidirectional"))
    )
    (net (code "131") (name "unconnected-(U$2-PadA11)") (class "Default")
      (node (ref "U$2") (pin "A11") (pinfunction "A11_A11") (pintype "bidirectional"))
    )
    (net (code "132") (name "unconnected-(U$2-PadA25)") (class "Default")
      (node (ref "U$2") (pin "A25") (pinfunction "A25_A25") (pintype "bidirectional"))
    )
    (net (code "133") (name "unconnected-(U$2-PadA26)") (class "Default")
      (node (ref "U$2") (pin "A26") (pinfunction "A26_A26") (pintype "bidirectional"))
    )
    (net (code "134") (name "unconnected-(U$2-PadDC)") (class "Default")
      (node (ref "U$2") (pin "DC") (pinfunction "DC_DC") (pintype "bidirectional"))
    )
    (net (code "135") (name "unconnected-(U$2-PadDE)") (class "Default")
      (node (ref "U$2") (pin "DE") (pinfunction "DE_DE") (pintype "bidirectional"))
    )
    (net (code "136") (name "unconnected-(U$2-PadDO)") (class "Default")
      (node (ref "U$2") (pin "DO") (pinfunction "DO_DO") (pintype "bidirectional"))
    )
    (net (code "137") (name "unconnected-(U$2-PadPGM)") (class "Default")
      (node (ref "U$2") (pin "PGM") (pinfunction "PGM_PGM") (pintype "bidirectional"))
    )
    (net (code "138") (name "unconnected-(U$2-PadRESET)") (class "Default")
      (node (ref "U$2") (pin "RESET") (pinfunction "RESET_RESET") (pintype "bidirectional"))
    )
    (net (code "139") (name "unconnected-(U$4-PadRING_SW)") (class "Default")
      (node (ref "U$4") (pin "RING_SW") (pinfunction "RING_SW_RING_SW") (pintype "bidirectional"))
    )
    (net (code "140") (name "unconnected-(U$7-Pad4)") (class "Default")
      (node (ref "U$7") (pin "4") (pinfunction "4_4") (pintype "passive"))
    )
    (net (code "141") (name "unconnected-(U$7-Pad7)") (class "Default")
      (node (ref "U$7") (pin "7") (pinfunction "7_7") (pintype "passive"))
    )
    (net (code "142") (name "unconnected-(U$7-Pad10)") (class "Default")
      (node (ref "U$7") (pin "10") (pinfunction "10_10") (pintype "passive"))
    )
    (net (code "143") (name "unconnected-(U$7-Pad13)") (class "Default")
      (node (ref "U$7") (pin "13") (pinfunction "13_13") (pintype "passive"))
    )
    (net (code "144") (name "unconnected-(U$7-Pad16)") (class "Default")
      (node (ref "U$7") (pin "16") (pinfunction "16_16") (pintype "passive"))
    )
    (net (code "145") (name "unconnected-(U$7-Pad19)") (class "Default")
      (node (ref "U$7") (pin "19") (pinfunction "19_19") (pintype "passive"))
    )
    (net (code "146") (name "unconnected-(U$7-Pad22)") (class "Default")
      (node (ref "U$7") (pin "22") (pinfunction "22_22") (pintype "passive"))
    )
    (net (code "147") (name "unconnected-(U$7-Pad25)") (class "Default")
      (node (ref "U$7") (pin "25") (pinfunction "25_25") (pintype "passive"))
    )
    (net (code "148") (name "unconnected-(U$8-Pad4)") (class "Default")
      (node (ref "U$8") (pin "4") (pinfunction "4_4") (pintype "passive"))
    )
    (net (code "149") (name "unconnected-(U$8-Pad7)") (class "Default")
      (node (ref "U$8") (pin "7") (pinfunction "7_7") (pintype "passive"))
    )
    (net (code "150") (name "unconnected-(U$8-Pad10)") (class "Default")
      (node (ref "U$8") (pin "10") (pinfunction "10_10") (pintype "passive"))
    )
    (net (code "151") (name "unconnected-(U$8-Pad13)") (class "Default")
      (node (ref "U$8") (pin "13") (pinfunction "13_13") (pintype "passive"))
    )
    (net (code "152") (name "unconnected-(U$8-Pad16)") (class "Default")
      (node (ref "U$8") (pin "16") (pinfunction "16_16") (pintype "passive"))
    )
    (net (code "153") (name "unconnected-(U$8-Pad19)") (class "Default")
      (node (ref "U$8") (pin "19") (pinfunction "19_19") (pintype "passive"))
    )
    (net (code "154") (name "unconnected-(U$8-Pad22)") (class "Default")
      (node (ref "U$8") (pin "22") (pinfunction "22_22") (pintype "passive"))
    )
    (net (code "155") (name "unconnected-(U$8-Pad25)") (class "Default")
      (node (ref "U$8") (pin "25") (pinfunction "25_25") (pintype "passive"))
    )
    (net (code "156") (name "unconnected-(U$9-Pad4)") (class "Default")
      (node (ref "U$9") (pin "4") (pinfunction "4_4") (pintype "passive"))
    )
    (net (code "157") (name "unconnected-(U$9-Pad7)") (class "Default")
      (node (ref "U$9") (pin "7") (pinfunction "7_7") (pintype "passive"))
    )
    (net (code "158") (name "unconnected-(U$9-Pad10)") (class "Default")
      (node (ref "U$9") (pin "10") (pinfunction "10_10") (pintype "passive"))
    )
    (net (code "159") (name "unconnected-(U$9-Pad13)") (class "Default")
      (node (ref "U$9") (pin "13") (pinfunction "13_13") (pintype "passive"))
    )
    (net (code "160") (name "unconnected-(U$9-Pad16)") (class "Default")
      (node (ref "U$9") (pin "16") (pinfunction "16_16") (pintype "passive"))
    )
    (net (code "161") (name "unconnected-(U$9-Pad19)") (class "Default")
      (node (ref "U$9") (pin "19") (pinfunction "19_19") (pintype "passive"))
    )
    (net (code "162") (name "unconnected-(U$9-Pad22)") (class "Default")
      (node (ref "U$9") (pin "22") (pinfunction "22_22") (pintype "passive"))
    )
    (net (code "163") (name "unconnected-(U$9-Pad25)") (class "Default")
      (node (ref "U$9") (pin "25") (pinfunction "25_25") (pintype "passive"))
    )
    (net (code "164") (name "unconnected-(U$14-Pad4)") (class "Default")
      (node (ref "U$14") (pin "4") (pinfunction "4_4") (pintype "passive"))
    )
    (net (code "165") (name "unconnected-(U$14-Pad7)") (class "Default")
      (node (ref "U$14") (pin "7") (pinfunction "7_7") (pintype "passive"))
    )
    (net (code "166") (name "unconnected-(U$14-Pad10)") (class "Default")
      (node (ref "U$14") (pin "10") (pinfunction "10_10") (pintype "passive"))
    )
    (net (code "167") (name "unconnected-(U$14-Pad13)") (class "Default")
      (node (ref "U$14") (pin "13") (pinfunction "13_13") (pintype "passive"))
    )
    (net (code "168") (name "unconnected-(U$14-Pad16)") (class "Default")
      (node (ref "U$14") (pin "16") (pinfunction "16_16") (pintype "passive"))
    )
    (net (code "169") (name "unconnected-(U$14-Pad19)") (class "Default")
      (node (ref "U$14") (pin "19") (pinfunction "19_19") (pintype "passive"))
    )
    (net (code "170") (name "unconnected-(U$14-Pad22)") (class "Default")
      (node (ref "U$14") (pin "22") (pinfunction "22_22") (pintype "passive"))
    )
    (net (code "171") (name "unconnected-(U$14-Pad25)") (class "Default")
      (node (ref "U$14") (pin "25") (pinfunction "25_25") (pintype "passive"))
    )
    (net (code "172") (name "unconnected-(U$15-Pad4)") (class "Default")
      (node (ref "U$15") (pin "4") (pinfunction "4_4") (pintype "passive"))
    )
    (net (code "173") (name "unconnected-(U$15-Pad7)") (class "Default")
      (node (ref "U$15") (pin "7") (pinfunction "7_7") (pintype "passive"))
    )
    (net (code "174") (name "unconnected-(U$15-Pad10)") (class "Default")
      (node (ref "U$15") (pin "10") (pinfunction "10_10") (pintype "passive"))
    )
    (net (code "175") (name "unconnected-(U$15-Pad13)") (class "Default")
      (node (ref "U$15") (pin "13") (pinfunction "13_13") (pintype "passive"))
    )
    (net (code "176") (name "unconnected-(U$15-Pad16)") (class "Default")
      (node (ref "U$15") (pin "16") (pinfunction "16_16") (pintype "passive"))
    )
    (net (code "177") (name "unconnected-(U$15-Pad19)") (class "Default")
      (node (ref "U$15") (pin "19") (pinfunction "19_19") (pintype "passive"))
    )
    (net (code "178") (name "unconnected-(U$15-Pad22)") (class "Default")
      (node (ref "U$15") (pin "22") (pinfunction "22_22") (pintype "passive"))
    )
    (net (code "179") (name "unconnected-(U$15-Pad25)") (class "Default")
      (node (ref "U$15") (pin "25") (pinfunction "25_25") (pintype "passive"))
    )
    (net (code "180") (name "unconnected-(U$17-Pad4)") (class "Default")
      (node (ref "U$17") (pin "4") (pinfunction "4_4") (pintype "passive"))
    )
    (net (code "181") (name "unconnected-(U$17-Pad7)") (class "Default")
      (node (ref "U$17") (pin "7") (pinfunction "7_7") (pintype "passive"))
    )
    (net (code "182") (name "unconnected-(U$17-Pad10)") (class "Default")
      (node (ref "U$17") (pin "10") (pinfunction "10_10") (pintype "passive"))
    )
    (net (code "183") (name "unconnected-(U$17-Pad13)") (class "Default")
      (node (ref "U$17") (pin "13") (pinfunction "13_13") (pintype "passive"))
    )
    (net (code "184") (name "unconnected-(U$17-Pad16)") (class "Default")
      (node (ref "U$17") (pin "16") (pinfunction "16_16") (pintype "passive"))
    )
    (net (code "185") (name "unconnected-(U$17-Pad19)") (class "Default")
      (node (ref "U$17") (pin "19") (pinfunction "19_19") (pintype "passive"))
    )
    (net (code "186") (name "unconnected-(U$17-Pad22)") (class "Default")
      (node (ref "U$17") (pin "22") (pinfunction "22_22") (pintype "passive"))
    )
    (net (code "187") (name "unconnected-(U$17-Pad25)") (class "Default")
      (node (ref "U$17") (pin "25") (pinfunction "25_25") (pintype "passive"))
    )
  )
)
